# PIC-ICSP-RST.net
KiCad netlist of a schematic drawn in Altium Designer
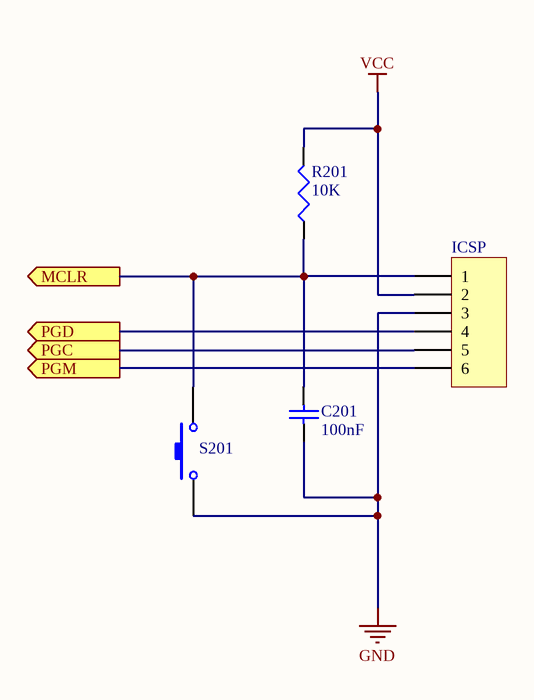
[diagram p0: PIC-ICSP-RST.SchDoc]

(export (version "E")
  (design (tool "Eeschema 10.0.6"))
  (components
    (comp (ref "C201")
      (value "100nF")
      (footprint "RCL 0805")
      (description "Capacitor (Semiconductor SIM Model)")
      (fields (field (name "Comment") "Cap Semi") (field (name "PUBLISHER") "Altium Limited"))
      (libsource (lib "Miscellaneous Devices") (part "Cap Semi"))
    )
    (comp (ref "ICSP")
      (value "Header 6")
      (footprint "MOLEX 22-23-2061")
      (description "Header, 6-Pin")
      (fields (field (name "PUBLISHER") "Altium Limited"))
      (libsource (lib "Miscellaneous Connectors") (part "Header 6"))
    )
    (comp (ref "R201")
      (value "10K")
      (footprint "RCL 0805")
      (description "Resistor")
      (fields (field (name "Comment") "Res3") (field (name "PUBLISHER") "Altium Limited"))
      (libsource (lib "Miscellaneous Devices") (part "Res3"))
    )
    (comp (ref "S201")
      (value "Reset Switch")
      (footprint "Square SMD Switch 01")
      (description "Switch")
      (fields (field (name "PUBLISHER") "Altium Limited"))
      (libsource (lib "Miscellaneous Devices") (part "SW-PB"))
    )
  )
  (nets
    (net (code "1") (name "/MCLR") (class "Default")
      (node (ref "C201") (pin "2") (pinfunction "2_2") (pintype "passive"))
      (node (ref "ICSP") (pin "1") (pinfunction "1_1") (pintype "passive"))
      (node (ref "R201") (pin "1") (pinfunction "1_1") (pintype "passive"))
      (node (ref "S201") (pin "2") (pinfunction "2_2") (pintype "passive"))
    )
    (net (code "2") (name "/PGC") (class "Default")
      (node (ref "ICSP") (pin "5") (pinfunction "5_5") (pintype "passive"))
    )
    (net (code "3") (name "/PGD") (class "Default")
      (node (ref "ICSP") (pin "4") (pinfunction "4_4") (pintype "passive"))
    )
    (net (code "4") (name "/PGM") (class "Default")
      (node (ref "ICSP") (pin "6") (pinfunction "6_6") (pintype "passive"))
    )
    (net (code "5") (name "GND") (class "Default")
      (node (ref "C201") (pin "1") (pinfunction "1_1") (pintype "passive"))
      (node (ref "ICSP") (pin "3") (pinfunction "3_3") (pintype "passive"))
      (node (ref "S201") (pin "1") (pinfunction "1_1") (pintype "passive"))
    )
    (net (code "6") (name "VCC") (class "Default")
      (node (ref "ICSP") (pin "2") (pinfunction "2_2") (pintype "passive"))
      (node (ref "R201") (pin "2") (pinfunction "2_2") (pintype "passive"))
    )
  )
)
